# PowerSupply.net
KiCad netlist of a schematic drawn in Altium Designer
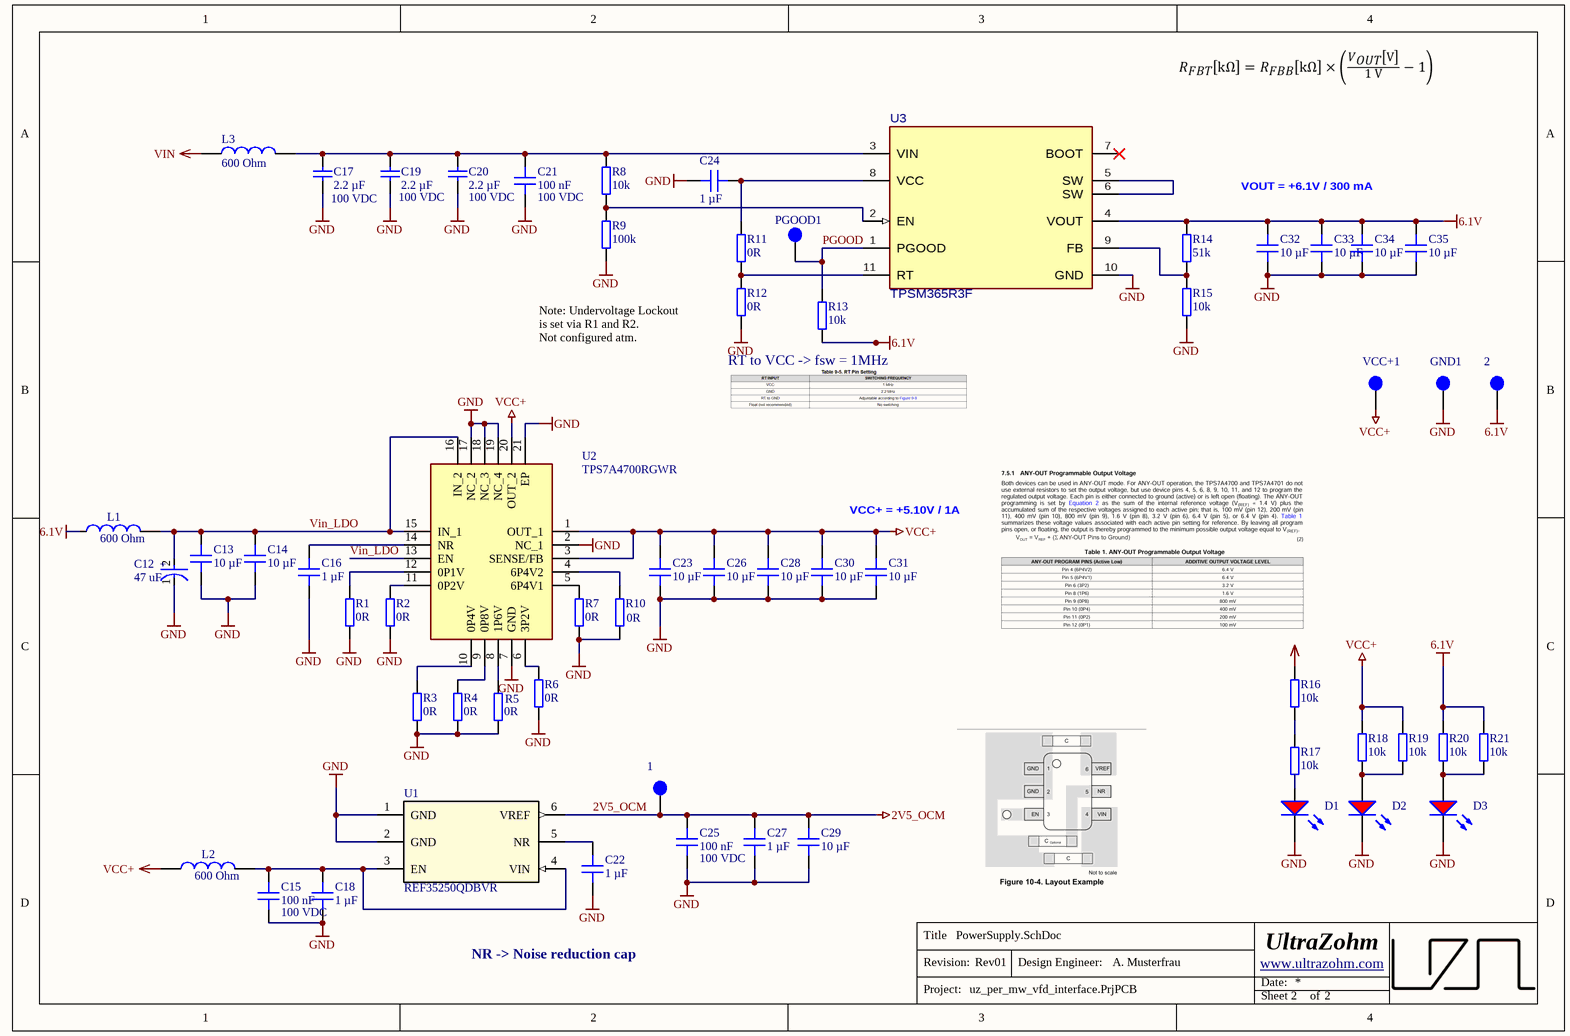
[diagram p0: PowerSupply.SchDoc]

(export (version "E")
  (design (tool "Eeschema 10.0.6"))
  (components
    (comp (ref "1")
      (value "2V5")
      (footprint "TP_1mm")
      (description "Testpoint 1mm")
      (fields
        (field (name "MANUFACTURER PART NUMBER") "NULL")
        (field (name "CREATED") "2018_06_25_AGeiger")
        (field (name "CREATED FROM") "AGeiger")
      )
      (libsource (lib "user") (part "TP_1mm"))
    )
    (comp (ref "2")
      (value "6.1V")
      (footprint "TP_1mm")
      (description "Testpoint 1mm")
      (fields
        (field (name "MANUFACTURER PART NUMBER") "NULL")
        (field (name "CREATED") "2018_06_25_AGeiger")
        (field (name "CREATED FROM") "AGeiger")
      )
      (libsource (lib "user") (part "TP_1mm"))
    )
    (comp (ref "C12")
      (value "47 uF")
      (footprint "10TPE47MAZB")
      (description "Tantalum Capacitors - Polymer 10volts 47uF ESR 35mohm")
      (fields
        (field (name "MANUFACTURER PART NUMBER") "10TPE47MAZB")
        (field (name "MANUFACTURER") "Panasonic")
        (field (name "CREATED FROM") "Kilhan")
      )
      (libsource (lib "user") (part "10TPE47MAZB"))
    )
    (comp (ref "C13")
      (value "10 µF")
      (footprint "C0805")
      (description "Capacitor 0805, 35 VDC, 10 µF, X5R")
      (fields
        (field (name "MANUFACTURER PART NUMBER") "GRM21BR6YA106KE43L")
        (field (name "MANUFACTURER") "muRata")
        (field (name "CREATED FROM") "MGremer")
      )
      (libsource (lib "user") (part "Capacitor"))
    )
    (comp (ref "C14")
      (value "10 µF")
      (footprint "C0805")
      (description "Capacitor 0805, 35 VDC, 10 µF, X5R")
      (fields
        (field (name "MANUFACTURER PART NUMBER") "GRM21BR6YA106KE43L")
        (field (name "MANUFACTURER") "muRata")
        (field (name "CREATED FROM") "MGremer")
      )
      (libsource (lib "user") (part "Capacitor"))
    )
    (comp (ref "C15")
      (value "100 nF")
      (footprint "C_0603")
      (description "100V 100nF X7S ±10% 0603 Multilayer Ceramic Capacitors MLCC - SMD/SMT ROHS")
      (fields
        (field (name "MANUFACTURER PART NUMBER") "C1608X7S2A104KT000N")
        (field (name "MANUFACTURER") "TDK")
        (field (name "VOLTAGE RATING") "100 VDC")
        (field (name "CREATED FROM") "AGeiger")
      )
      (libsource (lib "user") (part "Capacitor"))
    )
    (comp (ref "C16")
      (value "1 µF")
      (footprint "C_0603")
      (description "50V 1uF X5R ±10% 0603  Multilayer Ceramic Capacitors MLCC - SMD/SMT ROHS")
      (fields
        (field (name "MANUFACTURER PART NUMBER") "CL10A105KB8NNNC")
        (field (name "MANUFACTURER") "Samsung Electro-Mechanics")
        (field (name "CREATED FROM") "MGremer")
      )
      (libsource (lib "user") (part "Capacitor"))
    )
    (comp (ref "C17")
      (value "2.2 µF")
      (footprint "C_1210_TE")
      (description "100V 2.2uF X7R ±10% 1210 Multilayer Ceramic Capacitors MLCC - SMD/SMT ROHS")
      (fields
        (field (name "MANUFACTURER PART NUMBER") "FS32X225K101EGG")
        (field (name "MANUFACTURER") "PSA(Prosperity Dielectrics)")
        (field (name "VOLTAGE RATING") "100 VDC")
        (field (name "CREATED FROM") "AGeiger")
      )
      (libsource (lib "user") (part "CAP-NP"))
    )
    (comp (ref "C18")
      (value "1 µF")
      (footprint "C_0603")
      (description "50V 1uF X5R ±10% 0603  Multilayer Ceramic Capacitors MLCC - SMD/SMT ROHS")
      (fields
        (field (name "MANUFACTURER PART NUMBER") "CL10A105KB8NNNC")
        (field (name "MANUFACTURER") "Samsung Electro-Mechanics")
        (field (name "CREATED FROM") "MGremer")
      )
      (libsource (lib "user") (part "Capacitor"))
    )
    (comp (ref "C19")
      (value "2.2 µF")
      (footprint "C_1210_TE")
      (description "100V 2.2uF X7R ±10% 1210 Multilayer Ceramic Capacitors MLCC - SMD/SMT ROHS")
      (fields
        (field (name "MANUFACTURER PART NUMBER") "FS32X225K101EGG")
        (field (name "MANUFACTURER") "PSA(Prosperity Dielectrics)")
        (field (name "VOLTAGE RATING") "100 VDC")
        (field (name "CREATED FROM") "AGeiger")
      )
      (libsource (lib "user") (part "CAP-NP"))
    )
    (comp (ref "C20")
      (value "2.2 µF")
      (footprint "C_1210_TE")
      (description "100V 2.2uF X7R ±10% 1210 Multilayer Ceramic Capacitors MLCC - SMD/SMT ROHS")
      (fields
        (field (name "MANUFACTURER PART NUMBER") "FS32X225K101EGG")
        (field (name "MANUFACTURER") "PSA(Prosperity Dielectrics)")
        (field (name "VOLTAGE RATING") "100 VDC")
        (field (name "CREATED FROM") "AGeiger")
      )
      (libsource (lib "user") (part "CAP-NP"))
    )
    (comp (ref "C21")
      (value "100 nF")
      (footprint "C_0603")
      (description "100V 100nF X7S ±10% 0603 Multilayer Ceramic Capacitors MLCC - SMD/SMT ROHS")
      (fields
        (field (name "MANUFACTURER PART NUMBER") "C1608X7S2A104KT000N")
        (field (name "MANUFACTURER") "TDK")
        (field (name "VOLTAGE RATING") "100 VDC")
        (field (name "CREATED FROM") "AGeiger")
      )
      (libsource (lib "user") (part "Capacitor"))
    )
    (comp (ref "C22")
      (value "1 µF")
      (footprint "C_0603")
      (description "50V 1uF X5R ±10% 0603  Multilayer Ceramic Capacitors MLCC - SMD/SMT ROHS")
      (fields
        (field (name "MANUFACTURER PART NUMBER") "CL10A105KB8NNNC")
        (field (name "MANUFACTURER") "Samsung Electro-Mechanics")
        (field (name "CREATED FROM") "MGremer")
      )
      (libsource (lib "user") (part "Capacitor"))
    )
    (comp (ref "C23")
      (value "10 µF")
      (footprint "C0805")
      (description "Capacitor 0805, 35 VDC, 10 µF, X5R")
      (fields
        (field (name "MANUFACTURER PART NUMBER") "GRM21BR6YA106KE43L")
        (field (name "MANUFACTURER") "muRata")
        (field (name "CREATED FROM") "MGremer")
      )
      (libsource (lib "user") (part "Capacitor"))
    )
    (comp (ref "C24")
      (value "1 µF")
      (footprint "C_0603")
      (description "50V 1uF X5R ±10% 0603  Multilayer Ceramic Capacitors MLCC - SMD/SMT ROHS")
      (fields
        (field (name "MANUFACTURER PART NUMBER") "CL10A105KB8NNNC")
        (field (name "MANUFACTURER") "Samsung Electro-Mechanics")
        (field (name "CREATED FROM") "MGremer")
      )
      (libsource (lib "user") (part "Capacitor"))
    )
    (comp (ref "C25")
      (value "100 nF")
      (footprint "C_0603")
      (description "100V 100nF X7S ±10% 0603 Multilayer Ceramic Capacitors MLCC - SMD/SMT ROHS")
      (fields
        (field (name "MANUFACTURER PART NUMBER") "C1608X7S2A104KT000N")
        (field (name "MANUFACTURER") "TDK")
        (field (name "VOLTAGE RATING") "100 VDC")
        (field (name "CREATED FROM") "AGeiger")
      )
      (libsource (lib "user") (part "Capacitor"))
    )
    (comp (ref "C26")
      (value "10 µF")
      (footprint "C0805")
      (description "Capacitor 0805, 35 VDC, 10 µF, X5R")
      (fields
        (field (name "MANUFACTURER PART NUMBER") "GRM21BR6YA106KE43L")
        (field (name "MANUFACTURER") "muRata")
        (field (name "CREATED FROM") "MGremer")
      )
      (libsource (lib "user") (part "Capacitor"))
    )
    (comp (ref "C27")
      (value "1 µF")
      (footprint "C_0603")
      (description "50V 1uF X5R ±10% 0603  Multilayer Ceramic Capacitors MLCC - SMD/SMT ROHS")
      (fields
        (field (name "MANUFACTURER PART NUMBER") "CL10A105KB8NNNC")
        (field (name "MANUFACTURER") "Samsung Electro-Mechanics")
        (field (name "CREATED FROM") "MGremer")
      )
      (libsource (lib "user") (part "Capacitor"))
    )
    (comp (ref "C28")
      (value "10 µF")
      (footprint "C0805")
      (description "Capacitor 0805, 35 VDC, 10 µF, X5R")
      (fields
        (field (name "MANUFACTURER PART NUMBER") "GRM21BR6YA106KE43L")
        (field (name "MANUFACTURER") "muRata")
        (field (name "CREATED FROM") "MGremer")
      )
      (libsource (lib "user") (part "Capacitor"))
    )
    (comp (ref "C29")
      (value "10 µF")
      (footprint "C0805")
      (description "Capacitor 0805, 35 VDC, 10 µF, X5R")
      (fields
        (field (name "MANUFACTURER PART NUMBER") "GRM21BR6YA106KE43L")
        (field (name "MANUFACTURER") "muRata")
        (field (name "CREATED FROM") "MGremer")
      )
      (libsource (lib "user") (part "Capacitor"))
    )
    (comp (ref "C30")
      (value "10 µF")
      (footprint "C0805")
      (description "Capacitor 0805, 35 VDC, 10 µF, X5R")
      (fields
        (field (name "MANUFACTURER PART NUMBER") "GRM21BR6YA106KE43L")
        (field (name "MANUFACTURER") "muRata")
        (field (name "CREATED FROM") "MGremer")
      )
      (libsource (lib "user") (part "Capacitor"))
    )
    (comp (ref "C31")
      (value "10 µF")
      (footprint "C0805")
      (description "Capacitor 0805, 35 VDC, 10 µF, X5R")
      (fields
        (field (name "MANUFACTURER PART NUMBER") "GRM21BR6YA106KE43L")
        (field (name "MANUFACTURER") "muRata")
        (field (name "CREATED FROM") "MGremer")
      )
      (libsource (lib "user") (part "Capacitor"))
    )
    (comp (ref "C32")
      (value "10 µF")
      (footprint "C0805")
      (description "Capacitor 0805, 35 VDC, 10 µF, X5R")
      (fields
        (field (name "MANUFACTURER PART NUMBER") "GRM21BR6YA106KE43L")
        (field (name "MANUFACTURER") "muRata")
        (field (name "CREATED FROM") "MGremer")
      )
      (libsource (lib "user") (part "Capacitor"))
    )
    (comp (ref "C33")
      (value "10 µF")
      (footprint "C0805")
      (description "Capacitor 0805, 35 VDC, 10 µF, X5R")
      (fields
        (field (name "MANUFACTURER PART NUMBER") "GRM21BR6YA106KE43L")
        (field (name "MANUFACTURER") "muRata")
        (field (name "CREATED FROM") "MGremer")
      )
      (libsource (lib "user") (part "Capacitor"))
    )
    (comp (ref "C34")
      (value "10 µF")
      (footprint "C0805")
      (description "Capacitor 0805, 35 VDC, 10 µF, X5R")
      (fields
        (field (name "MANUFACTURER PART NUMBER") "GRM21BR6YA106KE43L")
        (field (name "MANUFACTURER") "muRata")
        (field (name "CREATED FROM") "MGremer")
      )
      (libsource (lib "user") (part "Capacitor"))
    )
    (comp (ref "C35")
      (value "10 µF")
      (footprint "C0805")
      (description "Capacitor 0805, 35 VDC, 10 µF, X5R")
      (fields
        (field (name "MANUFACTURER PART NUMBER") "GRM21BR6YA106KE43L")
        (field (name "MANUFACTURER") "muRata")
        (field (name "CREATED FROM") "MGremer")
      )
      (libsource (lib "user") (part "Capacitor"))
    )
    (comp (ref "D1")
      (value "KT-0603R")
      (footprint "WL-SMCW_0603")
      (description "LED RED 520~625NM 90~100MCD@20MA TOP VIEW 0603 ROHS")
      (fields
        (field (name "MANUFACTURER") "Hubei KENTO Elec")
        (field (name "LCSC PART NUMBER") "C2286")
        (field (name "CREATED FROM") "T. Wendt")
      )
      (libsource (lib "user") (part "LED_Red"))
    )
    (comp (ref "D2")
      (value "KT-0603R")
      (footprint "WL-SMCW_0603")
      (description "LED RED 520~625NM 90~100MCD@20MA TOP VIEW 0603 ROHS")
      (fields
        (field (name "MANUFACTURER") "Hubei KENTO Elec")
        (field (name "LCSC PART NUMBER") "C2286")
        (field (name "CREATED FROM") "T. Wendt")
      )
      (libsource (lib "user") (part "LED_Red"))
    )
    (comp (ref "D3")
      (value "KT-0603R")
      (footprint "WL-SMCW_0603")
      (description "LED RED 520~625NM 90~100MCD@20MA TOP VIEW 0603 ROHS")
      (fields
        (field (name "MANUFACTURER") "Hubei KENTO Elec")
        (field (name "LCSC PART NUMBER") "C2286")
        (field (name "CREATED FROM") "T. Wendt")
      )
      (libsource (lib "user") (part "LED_Red"))
    )
    (comp (ref "GND1")
      (value "Testpoint 1mm")
      (footprint "TP_1mm")
      (fields
        (field (name "MANUFACTURER PART NUMBER") "NULL")
        (field (name "CREATED") "2018_06_25_AGeiger")
        (field (name "CREATED FROM") "AGeiger")
      )
      (libsource (lib "user") (part "TP_1mm"))
    )
    (comp (ref "L1")
      (value "600 Ohm")
      (footprint "WE-CBF_0805_High Current")
      (description "Inductance, 0805, 100 MHz, 600 Ohm, 2 A")
      (fields
        (field (name "LCSC PART NUMBER") "C2661857")
        (field (name "MANUFACTURER PART NUMBER") "742792040")
        (field (name "CREATED FROM") "AGeiger")
      )
      (libsource (lib "user") (part "WE-CBF"))
    )
    (comp (ref "L2")
      (value "600 Ohm")
      (footprint "WE-CBF_0805_High Current")
      (description "Inductance, 0805, 100 MHz, 600 Ohm, 2 A")
      (fields
        (field (name "LCSC PART NUMBER") "C2661857")
        (field (name "MANUFACTURER PART NUMBER") "742792040")
        (field (name "CREATED FROM") "AGeiger")
      )
      (libsource (lib "user") (part "WE-CBF"))
    )
    (comp (ref "L3")
      (value "600 Ohm")
      (footprint "WE-CBF_0805_High Current")
      (description "Inductance, 0805, 100 MHz, 600 Ohm, 2 A")
      (fields
        (field (name "LCSC PART NUMBER") "C2661857")
        (field (name "MANUFACTURER PART NUMBER") "742792040")
        (field (name "CREATED FROM") "AGeiger")
      )
      (libsource (lib "user") (part "WE-CBF"))
    )
    (comp (ref "PGOOD1")
      (value "Testpoint 1mm")
      (footprint "TP_1mm")
      (fields
        (field (name "MANUFACTURER PART NUMBER") "NULL")
        (field (name "CREATED") "2018_06_25_AGeiger")
        (field (name "CREATED FROM") "AGeiger")
      )
      (libsource (lib "user") (part "TP_1mm"))
    )
    (comp (ref "R1")
      (value "0R")
      (footprint "RES 0603_1608")
      (description "SMD resistor E24 series")
      (fields
        (field (name "MANUFACTURER PART NUMBER") "RC0603JR-070RL")
        (field (name "MANUFACTURER") "YAGEO")
        (field (name "CREATED FROM") "MGremer")
      )
      (libsource (lib "user") (part "Resistor"))
    )
    (comp (ref "R2")
      (value "0R")
      (footprint "RES 0603_1608")
      (description "SMD resistor E24 series")
      (fields
        (field (name "MANUFACTURER PART NUMBER") "RC0603JR-070RL")
        (field (name "MANUFACTURER") "YAGEO")
        (field (name "CREATED FROM") "MGremer")
      )
      (libsource (lib "user") (part "Resistor"))
    )
    (comp (ref "R3")
      (value "0R")
      (footprint "RES 0603_1608")
      (description "SMD resistor E24 series")
      (fields
        (field (name "MANUFACTURER PART NUMBER") "RC0603JR-070RL")
        (field (name "MANUFACTURER") "YAGEO")
        (field (name "CREATED FROM") "MGremer")
      )
      (libsource (lib "user") (part "Resistor"))
    )
    (comp (ref "R4")
      (value "0R")
      (footprint "RES 0603_1608")
      (description "SMD resistor E24 series")
      (fields
        (field (name "MANUFACTURER PART NUMBER") "RC0603JR-070RL")
        (field (name "MANUFACTURER") "YAGEO")
        (field (name "CREATED FROM") "MGremer")
      )
      (libsource (lib "user") (part "Resistor"))
    )
    (comp (ref "R5")
      (value "0R")
      (footprint "RES 0603_1608")
      (description "SMD resistor E24 series")
      (fields
        (field (name "MANUFACTURER PART NUMBER") "RC0603JR-070RL")
        (field (name "MANUFACTURER") "YAGEO")
        (field (name "CREATED FROM") "MGremer")
      )
      (libsource (lib "user") (part "Resistor"))
    )
    (comp (ref "R6")
      (value "0R")
      (footprint "RES 0603_1608")
      (description "SMD resistor E24 series")
      (fields
        (field (name "MANUFACTURER PART NUMBER") "RC0603JR-070RL")
        (field (name "MANUFACTURER") "YAGEO")
        (field (name "CREATED FROM") "MGremer")
      )
      (libsource (lib "user") (part "Resistor"))
    )
    (comp (ref "R7")
      (value "0R")
      (footprint "RES 0603_1608")
      (description "SMD resistor E24 series")
      (fields
        (field (name "MANUFACTURER PART NUMBER") "RC0603JR-070RL")
        (field (name "MANUFACTURER") "YAGEO")
        (field (name "CREATED FROM") "MGremer")
      )
      (libsource (lib "user") (part "Resistor"))
    )
    (comp (ref "R8")
      (value "10k")
      (footprint "RES 0603_1608")
      (description "SMD resistor 1%")
      (fields
        (field (name "MANUFACTURER PART NUMBER") "0603WAF1002T5E")
        (field (name "MANUFACTURER") "UNI-ROYAL")
        (field (name "CREATED FROM") "AGeiger")
      )
      (libsource (lib "user") (part "Resistor"))
    )
    (comp (ref "R9")
      (value "100k")
      (footprint "RES 0603_1608")
      (description "SMD resistor 1%")
      (fields
        (field (name "MANUFACTURER PART NUMBER") "CRCW0603100KFKEAC")
        (field (name "MANUFACTURER") "Vishay")
        (field (name "CREATED FROM") "MGremer")
      )
      (libsource (lib "user") (part "Resistor"))
    )
    (comp (ref "R10")
      (value "0R")
      (footprint "RES 0603_1608")
      (description "SMD resistor E24 series")
      (fields
        (field (name "MANUFACTURER PART NUMBER") "RC0603JR-070RL")
        (field (name "MANUFACTURER") "YAGEO")
        (field (name "CREATED FROM") "MGremer")
      )
      (libsource (lib "user") (part "Resistor"))
    )
    (comp (ref "R11")
      (value "0R")
      (footprint "RES 0603_1608")
      (description "SMD resistor E24 series")
      (fields
        (field (name "MANUFACTURER PART NUMBER") "RC0603JR-070RL")
        (field (name "MANUFACTURER") "YAGEO")
        (field (name "CREATED FROM") "MGremer")
      )
      (libsource (lib "user") (part "Resistor"))
    )
    (comp (ref "R12")
      (value "0R")
      (footprint "RES 0603_1608")
      (description "SMD resistor E24 series")
      (fields
        (field (name "MANUFACTURER PART NUMBER") "RC0603JR-070RL")
        (field (name "MANUFACTURER") "YAGEO")
        (field (name "CREATED FROM") "MGremer")
      )
      (libsource (lib "user") (part "Resistor"))
    )
    (comp (ref "R13")
      (value "10k")
      (footprint "RES 0603_1608")
      (description "SMD resistor 1%")
      (fields
        (field (name "MANUFACTURER PART NUMBER") "0603WAF1002T5E")
        (field (name "MANUFACTURER") "UNI-ROYAL")
        (field (name "CREATED FROM") "AGeiger")
      )
      (libsource (lib "user") (part "Resistor"))
    )
    (comp (ref "R14")
      (value "51k")
      (footprint "R_0603_TE")
      (description "100mW Thick Film Resistors 75V ±100ppm/℃ ±1% 51kΩ 0603 Chip Resistor - Surface Mount ROHS")
      (fields
        (field (name "MANUFACTURER PART NUMBER") "0603WAF5102T5E")
        (field (name "MANUFACTURER") "UNI-ROYAL(Uniroyal Elec)")
        (field (name "CREATED FROM") "KIlhan")
      )
      (libsource (lib "user") (part "Resistor"))
    )
    (comp (ref "R15")
      (value "10k")
      (footprint "RES 0603_1608")
      (description "SMD resistor 1%")
      (fields
        (field (name "MANUFACTURER PART NUMBER") "0603WAF1002T5E")
        (field (name "MANUFACTURER") "UNI-ROYAL")
        (field (name "CREATED FROM") "AGeiger")
      )
      (libsource (lib "user") (part "Resistor"))
    )
    (comp (ref "R16")
      (value "10k")
      (footprint "RES 0603_1608")
      (description "SMD resistor 1%")
      (fields
        (field (name "MANUFACTURER PART NUMBER") "0603WAF1002T5E")
        (field (name "MANUFACTURER") "UNI-ROYAL")
        (field (name "CREATED FROM") "AGeiger")
      )
      (libsource (lib "user") (part "Resistor"))
    )
    (comp (ref "R17")
      (value "10k")
      (footprint "RES 0603_1608")
      (description "SMD resistor 1%")
      (fields
        (field (name "MANUFACTURER PART NUMBER") "0603WAF1002T5E")
        (field (name "MANUFACTURER") "UNI-ROYAL")
        (field (name "CREATED FROM") "AGeiger")
      )
      (libsource (lib "user") (part "Resistor"))
    )
    (comp (ref "R18")
      (value "10k")
      (footprint "RES 0603_1608")
      (description "SMD resistor 1%")
      (fields
        (field (name "MANUFACTURER PART NUMBER") "0603WAF1002T5E")
        (field (name "MANUFACTURER") "UNI-ROYAL")
        (field (name "CREATED FROM") "AGeiger")
      )
      (libsource (lib "user") (part "Resistor"))
    )
    (comp (ref "R19")
      (value "10k")
      (footprint "RES 0603_1608")
      (description "SMD resistor 1%")
      (fields
        (field (name "MANUFACTURER PART NUMBER") "0603WAF1002T5E")
        (field (name "MANUFACTURER") "UNI-ROYAL")
        (field (name "CREATED FROM") "AGeiger")
      )
      (libsource (lib "user") (part "Resistor"))
    )
    (comp (ref "R20")
      (value "10k")
      (footprint "RES 0603_1608")
      (description "SMD resistor 1%")
      (fields
        (field (name "MANUFACTURER PART NUMBER") "0603WAF1002T5E")
        (field (name "MANUFACTURER") "UNI-ROYAL")
        (field (name "CREATED FROM") "AGeiger")
      )
      (libsource (lib "user") (part "Resistor"))
    )
    (comp (ref "R21")
      (value "10k")
      (footprint "RES 0603_1608")
      (description "SMD resistor 1%")
      (fields
        (field (name "MANUFACTURER PART NUMBER") "0603WAF1002T5E")
        (field (name "MANUFACTURER") "UNI-ROYAL")
        (field (name "CREATED FROM") "AGeiger")
      )
      (libsource (lib "user") (part "Resistor"))
    )
    (comp (ref "U1")
      (value "REF35250QDBVR")
      (footprint "TI_SOT23_6-Leads")
      (description "2.5V ±0.05% 2.75V~6V 10mA Fixed SOT-23-6 Voltage Reference ROHS")
      (fields
        (field (name "MANUFACTURER") "Texas Instruments")
        (field (name "LCSC PART NUMBER") "C6265005")
        (field (name "CREATED FROM") "KIlhan")
      )
      (libsource (lib "user") (part "REF35250QDBVR"))
    )
    (comp (ref "U2")
      (value "TPS7A4700RGWR")
      (footprint "QFN65P500X500X100-21N-D")
      (description "1-A, 36-V, low-noise, high-PSRR, low-dropout voltage regulator with enable")
      (fields
        (field (name "MANUFACTURER_PART_NUMBER") "TPS7A4701RGWR")
        (field (name "MOUSER PART NUMBER") "595-TPS7A4701RGWR")
        (field (name "CREATED FROM") "KIlhan")
      )
      (libsource (lib "user") (part "TPS7A4701RGWR"))
    )
    (comp (ref "U3")
      (value "TPSM365R3F")
      (footprint "RDN0011A-MFG")
      (description "3-V to 65-V input, 1-V to 13-V output, 0.6-A synchronous buck converter power module")
      (fields
        (field (name "MANUFACTURER PART NUMBER") "TPSM365R3FRDNR")
        (field (name "MANUFACTURER") "Texas Instruments")
        (field (name "CREATED FROM") "KIlhan")
      )
      (libsource (lib "user") (part "TPSM365"))
    )
    (comp (ref "VCC+1")
      (value "VCC+")
      (footprint "TP_1mm")
      (description "Testpoint 1mm")
      (fields
        (field (name "MANUFACTURER PART NUMBER") "NULL")
        (field (name "CREATED") "2018_06_25_AGeiger")
        (field (name "CREATED FROM") "AGeiger")
      )
      (libsource (lib "user") (part "TP_1mm"))
    )
  )
  (nets
    (net (code "2") (name "/PGOOD") (class "Default")
      (node (ref "PGOOD1") (pin "1") (pintype "passive"))
      (node (ref "R13") (pin "1") (pinfunction "1_1") (pintype "passive"))
      (node (ref "U3") (pin "1") (pinfunction "PGOOD_1") (pintype "open_collector"))
    )
    (net (code "3") (name "/Vin_LDO") (class "Default")
      (node (ref "C12") (pin "2") (pinfunction "A_2") (pintype "passive"))
      (node (ref "C13") (pin "2") (pinfunction "2_2") (pintype "passive"))
      (node (ref "C14") (pin "2") (pinfunction "2_2") (pintype "passive"))
      (node (ref "L1") (pin "2") (pinfunction "2_2") (pintype "passive"))
      (node (ref "U2") (pin "13") (pinfunction "EN_13") (pintype "passive"))
      (node (ref "U2") (pin "15") (pinfunction "IN_1_15") (pintype "passive"))
      (node (ref "U2") (pin "16") (pinfunction "IN_2_16") (pintype "passive"))
    )
    (net (code "4") (name "2V5_OCM") (class "Default")
      (node (ref "1") (pin "1") (pintype "passive"))
      (node (ref "C25") (pin "2") (pinfunction "2_2") (pintype "passive"))
      (node (ref "C27") (pin "2") (pinfunction "2_2") (pintype "passive"))
      (node (ref "C29") (pin "2") (pinfunction "2_2") (pintype "passive"))
      (node (ref "U1") (pin "6") (pinfunction "VREF_6") (pintype "output"))
    )
    (net (code "5") (name "6.1V") (class "Default")
      (node (ref "2") (pin "1") (pintype "passive"))
      (node (ref "C32") (pin "2") (pinfunction "2_2") (pintype "passive"))
      (node (ref "C33") (pin "2") (pinfunction "2_2") (pintype "passive"))
      (node (ref "C34") (pin "2") (pinfunction "2_2") (pintype "passive"))
      (node (ref "C35") (pin "2") (pinfunction "2_2") (pintype "passive"))
      (node (ref "L1") (pin "1") (pinfunction "1_1") (pintype "passive"))
      (node (ref "R13") (pin "2") (pinfunction "2_2") (pintype "passive"))
      (node (ref "R14") (pin "2") (pinfunction "2_2") (pintype "passive"))
      (node (ref "R20") (pin "1") (pinfunction "1_1") (pintype "passive"))
      (node (ref "R21") (pin "1") (pinfunction "1_1") (pintype "passive"))
      (node (ref "U3") (pin "4") (pinfunction "VOUT_4") (pintype "power_in"))
    )
    (net (code "6") (name "GND") (class "Default")
      (node (ref "C12") (pin "1") (pinfunction "C_1") (pintype "passive"))
      (node (ref "C13") (pin "1") (pinfunction "1_1") (pintype "passive"))
      (node (ref "C14") (pin "1") (pinfunction "1_1") (pintype "passive"))
      (node (ref "C15") (pin "1") (pinfunction "1_1") (pintype "passive"))
      (node (ref "C16") (pin "2") (pinfunction "2_2") (pintype "passive"))
      (node (ref "C17") (pin "2") (pinfunction "2_2") (pintype "passive"))
      (node (ref "C18") (pin "1") (pinfunction "1_1") (pintype "passive"))
      (node (ref "C19") (pin "2") (pinfunction "2_2") (pintype "passive"))
      (node (ref "C20") (pin "2") (pinfunction "2_2") (pintype "passive"))
      (node (ref "C21") (pin "1") (pinfunction "1_1") (pintype "passive"))
      (node (ref "C22") (pin "1") (pinfunction "1_1") (pintype "passive"))
      (node (ref "C23") (pin "1") (pinfunction "1_1") (pintype "passive"))
      (node (ref "C24") (pin "2") (pinfunction "2_2") (pintype "passive"))
      (node (ref "C25") (pin "1") (pinfunction "1_1") (pintype "passive"))
      (node (ref "C26") (pin "1") (pinfunction "1_1") (pintype "passive"))
      (node (ref "C27") (pin "1") (pinfunction "1_1") (pintype "passive"))
      (node (ref "C28") (pin "1") (pinfunction "1_1") (pintype "passive"))
      (node (ref "C29") (pin "1") (pinfunction "1_1") (pintype "passive"))
      (node (ref "C30") (pin "1") (pinfunction "1_1") (pintype "passive"))
      (node (ref "C31") (pin "1") (pinfunction "1_1") (pintype "passive"))
      (node (ref "C32") (pin "1") (pinfunction "1_1") (pintype "passive"))
      (node (ref "C33") (pin "1") (pinfunction "1_1") (pintype "passive"))
      (node (ref "C34") (pin "1") (pinfunction "1_1") (pintype "passive"))
      (node (ref "C35") (pin "1") (pinfunction "1_1") (pintype "passive"))
      (node (ref "D1") (pin "1") (pinfunction "K_1") (pintype "passive"))
      (node (ref "D2") (pin "1") (pinfunction "K_1") (pintype "passive"))
      (node (ref "D3") (pin "1") (pinfunction "K_1") (pintype "passive"))
      (node (ref "GND1") (pin "1") (pintype "passive"))
      (node (ref "R1") (pin "2") (pinfunction "2_2") (pintype "passive"))
      (node (ref "R10") (pin "1") (pinfunction "1_1") (pintype "passive"))
      (node (ref "R12") (pin "1") (pinfunction "1_1") (pintype "passive"))
      (node (ref "R15") (pin "2") (pinfunction "2_2") (pintype "passive"))
      (node (ref "R2") (pin "1") (pinfunction "1_1") (pintype "passive"))
      (node (ref "R3") (pin "1") (pinfunction "1_1") (pintype "passive"))
      (node (ref "R4") (pin "1") (pinfunction "1_1") (pintype "passive"))
      (node (ref "R5") (pin "1") (pinfunction "1_1") (pintype "passive"))
      (node (ref "R6") (pin "2") (pinfunction "2_2") (pintype "passive"))
      (node (ref "R7") (pin "1") (pinfunction "1_1") (pintype "passive"))
      (node (ref "R9") (pin "2") (pinfunction "2_2") (pintype "passive"))
      (node (ref "U1") (pin "1") (pinfunction "GND_1") (pintype "power_in"))
      (node (ref "U1") (pin "2") (pinfunction "GND_2") (pintype "power_in"))
      (node (ref "U2") (pin "17") (pinfunction "NC_2_17") (pintype "passive"))
      (node (ref "U2") (pin "18") (pinfunction "NC_3_18") (pintype "passive"))
      (node (ref "U2") (pin "19") (pinfunction "NC_4_19") (pintype "passive"))
      (node (ref "U2") (pin "2") (pinfunction "NC_1_2") (pintype "passive"))
      (node (ref "U2") (pin "21") (pinfunction "EP_21") (pintype "passive"))
      (node (ref "U2") (pin "7") (pinfunction "GND_7") (pintype "passive"))
      (node (ref "U3") (pin "10") (pinfunction "GND_10") (pintype "power_in"))
    )
    (net (code "7") (name "Net-(D1-A)") (class "Default")
      (node (ref "D1") (pin "2") (pinfunction "A_2") (pintype "passive"))
      (node (ref "R17") (pin "2") (pinfunction "2_2") (pintype "passive"))
    )
    (net (code "8") (name "Net-(D2-A)") (class "Default")
      (node (ref "D2") (pin "2") (pinfunction "A_2") (pintype "passive"))
      (node (ref "R18") (pin "2") (pinfunction "2_2") (pintype "passive"))
      (node (ref "R19") (pin "2") (pinfunction "2_2") (pintype "passive"))
    )
    (net (code "9") (name "Net-(D3-A)") (class "Default")
      (node (ref "D3") (pin "2") (pinfunction "A_2") (pintype "passive"))
      (node (ref "R20") (pin "2") (pinfunction "2_2") (pintype "passive"))
      (node (ref "R21") (pin "2") (pinfunction "2_2") (pintype "passive"))
    )
    (net (code "10") (name "Net-(R16-Pad2)") (class "Default")
      (node (ref "R16") (pin "2") (pinfunction "2_2") (pintype "passive"))
      (node (ref "R17") (pin "1") (pinfunction "1_1") (pintype "passive"))
    )
    (net (code "11") (name "Net-(U1-EN)") (class "Default")
      (node (ref "C15") (pin "2") (pinfunction "2_2") (pintype "passive"))
      (node (ref "C18") (pin "2") (pinfunction "2_2") (pintype "passive"))
      (node (ref "L2") (pin "2") (pinfunction "2_2") (pintype "passive"))
      (node (ref "U1") (pin "3") (pinfunction "EN_3") (pintype "passive"))
      (node (ref "U1") (pin "4") (pinfunction "VIN_4") (pintype "input"))
    )
    (net (code "12") (name "Net-(U1-NR)") (class "Default")
      (node (ref "C22") (pin "2") (pinfunction "2_2") (pintype "passive"))
      (node (ref "U1") (pin "5") (pinfunction "NR_5") (pintype "passive"))
    )
    (net (code "13") (name "Net-(U2-0P1V)") (class "Default")
      (node (ref "R1") (pin "1") (pinfunction "1_1") (pintype "passive"))
      (node (ref "U2") (pin "12") (pinfunction "0P1V_12") (pintype "passive"))
    )
    (net (code "14") (name "Net-(U2-0P2V)") (class "Default")
      (node (ref "R2") (pin "2") (pinfunction "2_2") (pintype "passive"))
      (node (ref "U2") (pin "11") (pinfunction "0P2V_11") (pintype "passive"))
    )
    (net (code "15") (name "Net-(U2-0P4V)") (class "Default")
      (node (ref "R3") (pin "2") (pinfunction "2_2") (pintype "passive"))
      (node (ref "U2") (pin "10") (pinfunction "0P4V_10") (pintype "passive"))
    )
    (net (code "16") (name "Net-(U2-0P8V)") (class "Default")
      (node (ref "R4") (pin "2") (pinfunction "2_2") (pintype "passive"))
      (node (ref "U2") (pin "9") (pinfunction "0P8V_9") (pintype "passive"))
    )
    (net (code "17") (name "Net-(U2-1P6V)") (class "Default")
      (node (ref "R5") (pin "2") (pinfunction "2_2") (pintype "passive"))
      (node (ref "U2") (pin "8") (pinfunction "1P6V_8") (pintype "passive"))
    )
    (net (code "18") (name "Net-(U2-3P2V)") (class "Default")
      (node (ref "R6") (pin "1") (pinfunction "1_1") (pintype "passive"))
      (node (ref "U2") (pin "6") (pinfunction "3P2V_6") (pintype "passive"))
    )
    (net (code "19") (name "Net-(U2-6P4V1)") (class "Default")
      (node (ref "R7") (pin "2") (pinfunction "2_2") (pintype "passive"))
      (node (ref "U2") (pin "5") (pinfunction "6P4V1_5") (pintype "passive"))
    )
    (net (code "20") (name "Net-(U2-6P4V2)") (class "Default")
      (node (ref "R10") (pin "2") (pinfunction "2_2") (pintype "passive"))
      (node (ref "U2") (pin "4") (pinfunction "6P4V2_4") (pintype "passive"))
    )
    (net (code "21") (name "Net-(U2-NR)") (class "Default")
      (node (ref "C16") (pin "1") (pinfunction "1_1") (pintype "passive"))
      (node (ref "U2") (pin "14") (pinfunction "NR_14") (pintype "passive"))
    )
    (net (code "22") (name "Net-(U3-EN)") (class "Default")
      (node (ref "R8") (pin "1") (pinfunction "1_1") (pintype "passive"))
      (node (ref "R9") (pin "1") (pinfunction "1_1") (pintype "passive"))
      (node (ref "U3") (pin "2") (pinfunction "EN_2") (pintype "input"))
    )
    (net (code "23") (name "Net-(U3-FB)") (class "Default")
      (node (ref "R14") (pin "1") (pinfunction "1_1") (pintype "passive"))
      (node (ref "R15") (pin "1") (pinfunction "1_1") (pintype "passive"))
      (node (ref "U3") (pin "9") (pinfunction "FB_9") (pintype "passive"))
    )
    (net (code "24") (name "Net-(U3-RT)") (class "Default")
      (node (ref "R11") (pin "1") (pinfunction "1_1") (pintype "passive"))
      (node (ref "R12") (pin "2") (pinfunction "2_2") (pintype "passive"))
      (node (ref "U3") (pin "11") (pinfunction "RT_11") (pintype "passive"))
    )
    (net (code "25") (name "Net-(U3-SW-Pad5)") (class "Default")
      (node (ref "U3") (pin "5") (pinfunction "SW_5") (pintype "passive"))
      (node (ref "U3") (pin "6") (pinfunction "SW_6") (pintype "passive"))
    )
    (net (code "26") (name "Net-(U3-VCC)") (class "Default")
      (node (ref "C24") (pin "1") (pinfunction "1_1") (pintype "passive"))
      (node (ref "R11") (pin "2") (pinfunction "2_2") (pintype "passive"))
      (node (ref "U3") (pin "8") (pinfunction "VCC_8") (pintype "power_in"))
    )
    (net (code "27") (name "Net-(U3-VIN)") (class "Default")
      (node (ref "C17") (pin "1") (pinfunction "1_1") (pintype "passive"))
      (node (ref "C19") (pin "1") (pinfunction "1_1") (pintype "passive"))
      (node (ref "C20") (pin "1") (pinfunction "1_1") (pintype "passive"))
      (node (ref "C21") (pin "2") (pinfunction "2_2") (pintype "passive"))
      (node (ref "L3") (pin "2") (pinfunction "2_2") (pintype "passive"))
      (node (ref "R8") (pin "2") (pinfunction "2_2") (pintype "passive"))
      (node (ref "U3") (pin "3") (pinfunction "VIN_3") (pintype "power_in"))
    )
    (net (code "28") (name "VCC+") (class "Default")
      (node (ref "C23") (pin "2") (pinfunction "2_2") (pintype "passive"))
      (node (ref "C26") (pin "2") (pinfunction "2_2") (pintype "passive"))
      (node (ref "C28") (pin "2") (pinfunction "2_2") (pintype "passive"))
      (node (ref "C30") (pin "2") (pinfunction "2_2") (pintype "passive"))
      (node (ref "C31") (pin "2") (pinfunction "2_2") (pintype "passive"))
      (node (ref "L2") (pin "1") (pinfunction "1_1") (pintype "passive"))
      (node (ref "R18") (pin "1") (pinfunction "1_1") (pintype "passive"))
      (node (ref "R19") (pin "1") (pinfunction "1_1") (pintype "passive"))
      (node (ref "U2") (pin "1") (pinfunction "OUT_1_1") (pintype "passive"))
      (node (ref "U2") (pin "20") (pinfunction "OUT_2_20") (pintype "passive"))
      (node (ref "U2") (pin "3") (pinfunction "SENSE/FB_3") (pintype "passive"))
      (node (ref "VCC+1") (pin "1") (pintype "passive"))
    )
    (net (code "29") (name "VIN") (class "Default")
      (node (ref "L3") (pin "1") (pinfunction "1_1") (pintype "passive"))
      (node (ref "R16") (pin "1") (pinfunction "1_1") (pintype "passive"))
    )
    (net (code "30") (name "unconnected-(U3-BOOT-Pad7)") (class "Default")
      (node (ref "U3") (pin "7") (pinfunction "BOOT_7") (pintype "passive+no_connect"))
    )
  )
)
